# energy_meter_blk.net
KiCad netlist of a schematic drawn in Altium Designer
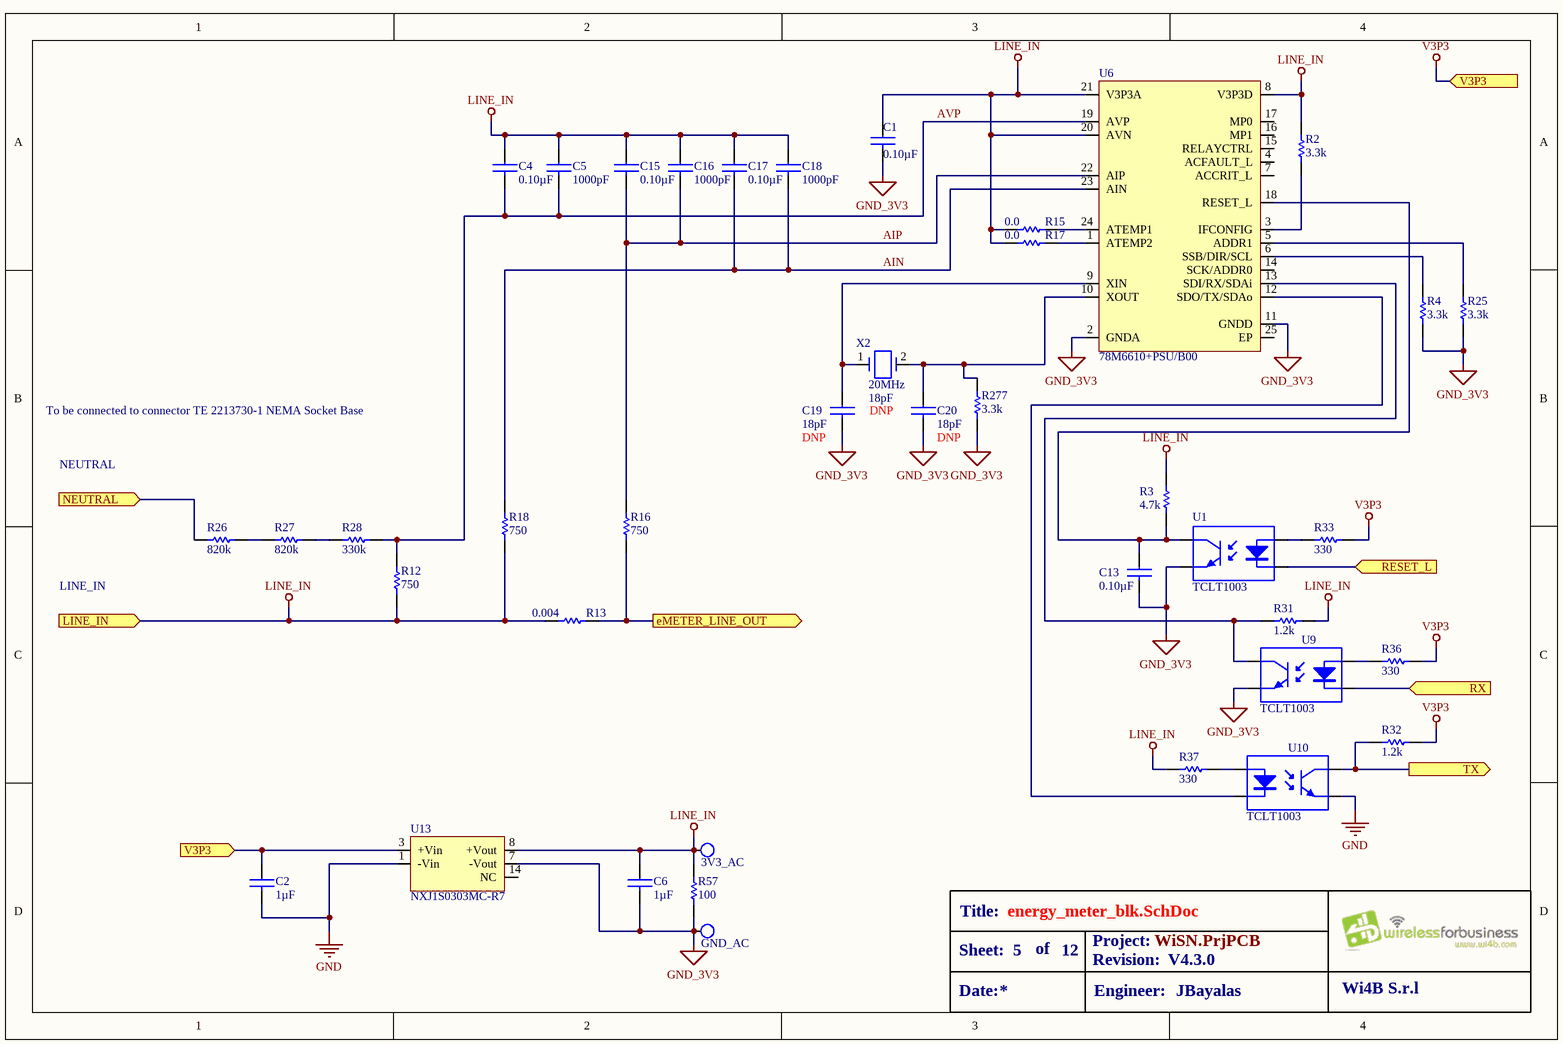
[diagram p0: energy_meter_blk.SchDoc]

(export (version "E")
  (design (tool "Eeschema 10.0.6"))
  (components
    (comp (ref "3V3_AC")
      (value "TestPad TH")
      (footprint "TestPad TH")
      (libsource (lib "Wilamp-st") (part "TestPad TH"))
    )
    (comp (ref "C1")
      (value "0.10µF")
      (footprint "C0402")
      (description "CAP CER 0.1UF 50V X7R 0402")
      (fields (field (name "MPN") "GRM155R71H104ME14D"))
      (libsource (lib "Capacitor") (part "GRM155R71H104ME14D"))
    )
    (comp (ref "C2")
      (value "1µF")
      (footprint "C0603")
      (description "CAP CER 1UF 16V X7R 0603")
      (fields (field (name "MPN") "GRM188R71C105KA12D"))
      (libsource (lib "Capacitor") (part "GRM188R71C105KA12D"))
    )
    (comp (ref "C4")
      (value "0.10µF")
      (footprint "C0402")
      (description "CAP CER 0.1UF 50V X7R 0402")
      (fields (field (name "MPN") "GRM155R71H104ME14D"))
      (libsource (lib "Capacitor") (part "GRM155R71H104ME14D"))
    )
    (comp (ref "C5")
      (value "1000pF")
      (footprint "C0402")
      (description "CAP CER 1000PF 50V NP0 0402")
      (fields (field (name "MPN") "GRM1555C1H102JA01D"))
      (libsource (lib "Capacitor") (part "GRM1555C1H102JA01D"))
    )
    (comp (ref "C6")
      (value "1µF")
      (footprint "C0603")
      (description "CAP CER 1UF 16V X7R 0603")
      (fields (field (name "MPN") "GRM188R71C105KA12D"))
      (libsource (lib "Capacitor") (part "GRM188R71C105KA12D"))
    )
    (comp (ref "C13")
      (value "0.10µF")
      (footprint "C0402")
      (description "CAP CER 0.1UF 50V X7R 0402")
      (fields (field (name "MPN") "GRM155R71H104ME14D"))
      (libsource (lib "Capacitor") (part "GRM155R71H104ME14D"))
    )
    (comp (ref "C15")
      (value "0.10µF")
      (footprint "C0402")
      (description "CAP CER 0.1UF 50V X7R 0402")
      (fields (field (name "MPN") "GRM155R71H104ME14D"))
      (libsource (lib "Capacitor") (part "GRM155R71H104ME14D"))
    )
    (comp (ref "C16")
      (value "1000pF")
      (footprint "C0402")
      (description "CAP CER 1000PF 50V NP0 0402")
      (fields (field (name "MPN") "GRM1555C1H102JA01D"))
      (libsource (lib "Capacitor") (part "GRM1555C1H102JA01D"))
    )
    (comp (ref "C17")
      (value "0.10µF")
      (footprint "C0402")
      (description "CAP CER 0.1UF 50V X7R 0402")
      (fields (field (name "MPN") "GRM155R71H104ME14D"))
      (libsource (lib "Capacitor") (part "GRM155R71H104ME14D"))
    )
    (comp (ref "C18")
      (value "1000pF")
      (footprint "C0402")
      (description "CAP CER 1000PF 50V NP0 0402")
      (fields (field (name "MPN") "GRM1555C1H102JA01D"))
      (libsource (lib "Capacitor") (part "GRM1555C1H102JA01D"))
    )
    (comp (ref "C19")
      (value "18pF")
      (footprint "C0402")
      (description "CAP CER 18PF 50V NP0 0402")
      (fields (field (name "MPN") "GRM1555C1H180FA01D") (field (name "DNP") "DNP"))
      (libsource (lib "Capacitor") (part "GRM1555C1H180FA01D"))
    )
    (comp (ref "C20")
      (value "18pF")
      (footprint "C0402")
      (description "CAP CER 18PF 50V NP0 0402")
      (fields (field (name "MPN") "GRM1555C1H180FA01D") (field (name "DNP") "DNP"))
      (libsource (lib "Capacitor") (part "GRM1555C1H180FA01D"))
    )
    (comp (ref "GND_AC")
      (value "TestPad TH")
      (footprint "TestPad TH")
      (libsource (lib "Wilamp-st") (part "TestPad TH"))
    )
    (comp (ref "R2")
      (value "3.3k")
      (footprint "R0402")
      (description "RES SMD 3.3K OHM 1% 1/16W 0402")
      (fields (field (name "MPN") "CRCW04023K30FKED"))
      (libsource (lib "Res") (part "CRCW04023K30FKED"))
    )
    (comp (ref "R3")
      (value "4.7k")
      (footprint "R0402")
      (description "RES SMD 4.7K OHM 1% 1/10W 0402")
      (fields (field (name "MPN") "ERJ-2RKF4701X"))
      (libsource (lib "Res") (part "ERJ-2RKF4701X"))
    )
    (comp (ref "R4")
      (value "3.3k")
      (footprint "R0402")
      (description "RES SMD 3.3K OHM 1% 1/16W 0402")
      (fields (field (name "MPN") "CRCW04023K30FKED"))
      (libsource (lib "Res") (part "CRCW04023K30FKED"))
    )
    (comp (ref "R12")
      (value "750")
      (footprint "R0603")
      (description "RES SMD 750 OHM 1% 1/10W 0603")
      (fields (field (name "MPN") "CRCW0603750RFKEA"))
      (libsource (lib "Res") (part "CRCW0603750RFKEA"))
    )
    (comp (ref "R13")
      (value "CRE2512-FZ-R004E-3")
      (footprint "R2512")
      (description "RES SMD 0.004 OHM 1% 3W 2512")
      (fields
        (field (name "MANUFACTURER") "Bourns Inc.")
        (field (name "TOLERANCE") "±1%")
        (field (name "RESISTANCE (OHMS)") "0.004")
      )
      (libsource (lib "Wilamp") (part "CRE2512-FZ-R004E-3"))
    )
    (comp (ref "R15")
      (value "0.0")
      (footprint "R0603")
      (description "RES SMD 0.0OHM JUMPER 1/10W 0603")
      (fields (field (name "MPN") "CRCW06030000Z0EA"))
      (libsource (lib "Res") (part "CRCW06030000Z0EA"))
    )
    (comp (ref "R16")
      (value "750")
      (footprint "R0603")
      (description "RES SMD 750 OHM 1% 1/10W 0603")
      (fields (field (name "MPN") "CRCW0603750RFKEA"))
      (libsource (lib "Res") (part "CRCW0603750RFKEA"))
    )
    (comp (ref "R17")
      (value "0.0")
      (footprint "R0603")
      (description "RES SMD 0.0OHM JUMPER 1/10W 0603")
      (fields (field (name "MPN") "CRCW06030000Z0EA"))
      (libsource (lib "Res") (part "CRCW06030000Z0EA"))
    )
    (comp (ref "R18")
      (value "750")
      (footprint "R0603")
      (description "RES SMD 750 OHM 1% 1/10W 0603")
      (fields (field (name "MPN") "CRCW0603750RFKEA"))
      (libsource (lib "Res") (part "CRCW0603750RFKEA"))
    )
    (comp (ref "R25")
      (value "3.3k")
      (footprint "R0402")
      (description "RES SMD 3.3K OHM 1% 1/16W 0402")
      (fields (field (name "MPN") "CRCW04023K30FKED"))
      (libsource (lib "Res") (part "CRCW04023K30FKED"))
    )
    (comp (ref "R26")
      (value "820k")
      (footprint "R1206")
      (description "RES SMD 820K OHM 1% 1/4W 1206")
      (fields (field (name "MPN") "CRCW1206820KFKEA"))
      (libsource (lib "Res") (part "CRCW1206820KFKEA"))
    )
    (comp (ref "R27")
      (value "820k")
      (footprint "R1206")
      (description "RES SMD 820K OHM 1% 1/4W 1206")
      (fields (field (name "MPN") "CRCW1206820KFKEA"))
      (libsource (lib "Res") (part "CRCW1206820KFKEA"))
    )
    (comp (ref "R28")
      (value "330k")
      (footprint "R1206")
      (description "RES SMD 330K OHM 1% 1/4W 1206")
      (fields (field (name "MPN") "CRCW1206330KFKEA"))
      (libsource (lib "Res") (part "CRCW1206330KFKEA"))
    )
    (comp (ref "R31")
      (value "1.2k")
      (footprint "RESC1005X40N")
      (description "RES SMD 1.2K OHM 1% 1/16W 0402")
      (fields (field (name "MPN") "RC0402FR-071K2L"))
      (libsource (lib "Res") (part "RC0402FR-071K2L"))
    )
    (comp (ref "R32")
      (value "1.2k")
      (footprint "RESC1005X40N")
      (description "RES SMD 1.2K OHM 1% 1/16W 0402")
      (fields (field (name "MPN") "RC0402FR-071K2L"))
      (libsource (lib "Res") (part "RC0402FR-071K2L"))
    )
    (comp (ref "R33")
      (value "330")
      (footprint "R0402")
      (description "RES SMD 330 OHM 1% 1/16W 0402")
      (fields (field (name "MPN") "CRCW0402330RFKED"))
      (libsource (lib "Res") (part "CRCW0402330RFKED"))
    )
    (comp (ref "R36")
      (value "330")
      (footprint "R0402")
      (description "RES SMD 330 OHM 1% 1/16W 0402")
      (fields (field (name "MPN") "CRCW0402330RFKED"))
      (libsource (lib "Res") (part "CRCW0402330RFKED"))
    )
    (comp (ref "R37")
      (value "330")
      (footprint "R0402")
      (description "RES SMD 330 OHM 1% 1/16W 0402")
      (fields (field (name "MPN") "CRCW0402330RFKED"))
      (libsource (lib "Res") (part "CRCW0402330RFKED"))
    )
    (comp (ref "R57")
      (value "100")
      (footprint "R1206")
      (description "RES 100 OHM 5% 1/4W 1206")
      (fields (field (name "MPN") "RMCF1206JT100R"))
      (libsource (lib "Res") (part "RMCF1206JT100R"))
    )
    (comp (ref "R277")
      (value "3.3k")
      (footprint "R0402")
      (description "RES SMD 3.3K OHM 1% 1/16W 0402")
      (fields (field (name "MPN") "CRCW04023K30FKED"))
      (libsource (lib "Res") (part "CRCW04023K30FKED"))
    )
    (comp (ref "U1")
      (value "TCLT1003")
      (footprint "SOP-4L")
      (description "OPTOISOLATR 5KV TRANSISTOR 4-SOP")
      (fields (field (name "MPN") "TCLT1003"))
      (libsource (lib "IC") (part "TCLT1003"))
    )
    (comp (ref "U6")
      (value "78M6610+PSU/B00")
      (footprint "QFN-24 (4X4mm)")
      (description "IC ENERGY MEASURMENT 1PH 24TQFN")
      (fields
        (field (name "MANUFACTURER") "Maxim Integrated")
        (field (name "MANUFACTURER PART NUMBER") "78M6610+PSU/B00")
      )
      (libsource (lib "Wilamp") (part "78M6610+PSU/B00"))
    )
    (comp (ref "U9")
      (value "TCLT1003")
      (footprint "SOP-4L")
      (description "OPTOISOLATR 5KV TRANSISTOR 4-SOP")
      (fields (field (name "MPN") "TCLT1003"))
      (libsource (lib "IC") (part "TCLT1003"))
    )
    (comp (ref "U10")
      (value "TCLT1003")
      (footprint "SOP-4L")
      (description "OPTOISOLATR 5KV TRANSISTOR 4-SOP")
      (fields (field (name "MPN") "TCLT1003"))
      (libsource (lib "IC") (part "TCLT1003"))
    )
    (comp (ref "U13")
      (value "NXJ1S0303MC-R7")
      (footprint "NXJ1S0303MC-R7")
      (description "Isolated DC/DC Converters 1W 3.3Vin 3.3Vout 333mA SM")
      (fields (field (name "MPN") "NXJ1S0303MC-R7"))
      (libsource (lib "IC") (part "NXJ1S0303MC-R7"))
    )
    (comp (ref "X2")
      (value "ABLS7M-20.000MHZ-B-2-T")
      (footprint "ABLS7M (crystal)")
      (description "CRYSTAL 20.000 MHZ 18PF SMT")
      (fields
        (field (name "MANUFACTURER") "Abracon LLC")
        (field (name "FREQUENCY") "20MHz")
        (field (name "LOAD CAPACITANCE") "18pF")
        (field (name "DNP") "DNP")
      )
      (libsource (lib "Wilamp") (part "ABLS7M-20.000MHZ-B-2-T"))
    )
  )
  (nets
    (net (code "1") (name "/AIN") (class "Default")
      (node (ref "C17") (pin "2") (pinfunction "2_2") (pintype "passive"))
      (node (ref "C18") (pin "2") (pinfunction "2_2") (pintype "passive"))
      (node (ref "R18") (pin "2") (pinfunction "2_2") (pintype "passive"))
      (node (ref "U6") (pin "23") (pinfunction "AIN_23") (pintype "passive"))
    )
    (net (code "2") (name "/AIP") (class "Default")
      (node (ref "C15") (pin "2") (pinfunction "2_2") (pintype "passive"))
      (node (ref "C16") (pin "2") (pinfunction "2_2") (pintype "passive"))
      (node (ref "R16") (pin "2") (pinfunction "2_2") (pintype "passive"))
      (node (ref "U6") (pin "22") (pinfunction "AIP_22") (pintype "passive"))
    )
    (net (code "3") (name "/AVP") (class "Default")
      (node (ref "C4") (pin "2") (pinfunction "2_2") (pintype "passive"))
      (node (ref "C5") (pin "2") (pinfunction "2_2") (pintype "passive"))
      (node (ref "R12") (pin "2") (pinfunction "2_2") (pintype "passive"))
      (node (ref "R28") (pin "2") (pinfunction "2_2") (pintype "passive"))
      (node (ref "U6") (pin "19") (pinfunction "AVP_19") (pintype "passive"))
    )
    (net (code "4") (name "/NEUTRAL") (class "Default")
      (node (ref "R26") (pin "1") (pinfunction "1_1") (pintype "passive"))
    )
    (net (code "5") (name "/RESET_L") (class "Default")
      (node (ref "U1") (pin "2") (pinfunction "K_2") (pintype "passive"))
    )
    (net (code "6") (name "/RX") (class "Default")
      (node (ref "U9") (pin "2") (pinfunction "K_2") (pintype "passive"))
    )
    (net (code "7") (name "/TX") (class "Default")
      (node (ref "R32") (pin "1") (pinfunction "1_1") (pintype "passive"))
      (node (ref "U10") (pin "4") (pinfunction "A/K_4") (pintype "passive"))
    )
    (net (code "8") (name "/eMETER_LINE_OUT") (class "Default")
      (node (ref "R13") (pin "2") (pinfunction "2_2") (pintype "passive"))
      (node (ref "R16") (pin "1") (pinfunction "1_1") (pintype "passive"))
    )
    (net (code "9") (name "GND") (class "Default")
      (node (ref "C2") (pin "2") (pinfunction "2_2") (pintype "passive"))
      (node (ref "U10") (pin "3") (pinfunction "A/K_3") (pintype "passive"))
      (node (ref "U13") (pin "1") (pinfunction "-Vin_1") (pintype "passive"))
    )
    (net (code "10") (name "GND_3V3") (class "Default")
      (node (ref "C1") (pin "2") (pinfunction "2_2") (pintype "passive"))
      (node (ref "C13") (pin "2") (pinfunction "2_2") (pintype "passive"))
      (node (ref "C19") (pin "2") (pinfunction "2_2") (pintype "passive"))
      (node (ref "C20") (pin "2") (pinfunction "2_2") (pintype "passive"))
      (node (ref "C6") (pin "2") (pinfunction "2_2") (pintype "passive"))
      (node (ref "GND_AC") (pin "1") (pinfunction "1_1") (pintype "passive"))
      (node (ref "R25") (pin "1") (pinfunction "1_1") (pintype "passive"))
      (node (ref "R277") (pin "1") (pinfunction "1_1") (pintype "passive"))
      (node (ref "R4") (pin "1") (pinfunction "1_1") (pintype "passive"))
      (node (ref "R57") (pin "2") (pinfunction "2_2") (pintype "passive"))
      (node (ref "U1") (pin "3") (pinfunction "A/K_3") (pintype "passive"))
      (node (ref "U13") (pin "7") (pinfunction "-Vout_7") (pintype "passive"))
      (node (ref "U6") (pin "11") (pinfunction "GNDD_11") (pintype "passive"))
      (node (ref "U6") (pin "2") (pinfunction "GNDA_2") (pintype "passive"))
      (node (ref "U9") (pin "3") (pinfunction "A/K_3") (pintype "passive"))
    )
    (net (code "11") (name "LINE_IN") (class "Default")
      (node (ref "3V3_AC") (pin "1") (pinfunction "1_1") (pintype "passive"))
      (node (ref "C1") (pin "1") (pinfunction "1_1") (pintype "passive"))
      (node (ref "C15") (pin "1") (pinfunction "1_1") (pintype "passive"))
      (node (ref "C16") (pin "1") (pinfunction "1_1") (pintype "passive"))
      (node (ref "C17") (pin "1") (pinfunction "1_1") (pintype "passive"))
      (node (ref "C18") (pin "1") (pinfunction "1_1") (pintype "passive"))
      (node (ref "C4") (pin "1") (pinfunction "1_1") (pintype "passive"))
      (node (ref "C5") (pin "1") (pinfunction "1_1") (pintype "passive"))
      (node (ref "C6") (pin "1") (pinfunction "1_1") (pintype "passive"))
      (node (ref "R12") (pin "1") (pinfunction "1_1") (pintype "passive"))
      (node (ref "R13") (pin "1") (pinfunction "1_1") (pintype "passive"))
      (node (ref "R15") (pin "1") (pinfunction "1_1") (pintype "passive"))
      (node (ref "R17") (pin "1") (pinfunction "1_1") (pintype "passive"))
      (node (ref "R18") (pin "1") (pinfunction "1_1") (pintype "passive"))
      (node (ref "R2") (pin "2") (pinfunction "2_2") (pintype "passive"))
      (node (ref "R3") (pin "2") (pinfunction "2_2") (pintype "passive"))
      (node (ref "R31") (pin "2") (pinfunction "2_2") (pintype "passive"))
      (node (ref "R37") (pin "1") (pinfunction "1_1") (pintype "passive"))
      (node (ref "R57") (pin "1") (pinfunction "1_1") (pintype "passive"))
      (node (ref "U13") (pin "8") (pinfunction "+Vout_8") (pintype "passive"))
      (node (ref "U6") (pin "20") (pinfunction "AVN_20") (pintype "passive"))
      (node (ref "U6") (pin "21") (pinfunction "V3P3A_21") (pintype "passive"))
      (node (ref "U6") (pin "8") (pinfunction "V3P3D_8") (pintype "passive"))
    )
    (net (code "12") (name "Net-(R26-Pad2)") (class "Default")
      (node (ref "R26") (pin "2") (pinfunction "2_2") (pintype "passive"))
      (node (ref "R27") (pin "1") (pinfunction "1_1") (pintype "passive"))
    )
    (net (code "13") (name "Net-(R27-Pad2)") (class "Default")
      (node (ref "R27") (pin "2") (pinfunction "2_2") (pintype "passive"))
      (node (ref "R28") (pin "1") (pinfunction "1_1") (pintype "passive"))
    )
    (net (code "14") (name "Net-(U1-A)") (class "Default")
      (node (ref "R33") (pin "1") (pinfunction "1_1") (pintype "passive"))
      (node (ref "U1") (pin "1") (pinfunction "A_1") (pintype "passive"))
    )
    (net (code "15") (name "Net-(U6-ADDR1)") (class "Default")
      (node (ref "R25") (pin "2") (pinfunction "2_2") (pintype "passive"))
      (node (ref "U6") (pin "5") (pinfunction "ADDR1_5") (pintype "passive"))
    )
    (net (code "16") (name "Net-(U6-ATEMP1)") (class "Default")
      (node (ref "R15") (pin "2") (pinfunction "2_2") (pintype "passive"))
      (node (ref "U6") (pin "24") (pinfunction "ATEMP1_24") (pintype "passive"))
    )
    (net (code "17") (name "Net-(U6-ATEMP2)") (class "Default")
      (node (ref "R17") (pin "2") (pinfunction "2_2") (pintype "passive"))
      (node (ref "U6") (pin "1") (pinfunction "ATEMP2_1") (pintype "passive"))
    )
    (net (code "18") (name "Net-(U6-IFCONFIG)") (class "Default")
      (node (ref "R2") (pin "1") (pinfunction "1_1") (pintype "passive"))
      (node (ref "U6") (pin "3") (pinfunction "IFCONFIG_3") (pintype "passive"))
    )
    (net (code "19") (name "Net-(U6-RESET_L)") (class "Default")
      (node (ref "C13") (pin "1") (pinfunction "1_1") (pintype "passive"))
      (node (ref "R3") (pin "1") (pinfunction "1_1") (pintype "passive"))
      (node (ref "U1") (pin "4") (pinfunction "A/K_4") (pintype "passive"))
      (node (ref "U6") (pin "18") (pinfunction "RESET_L_18") (pintype "passive"))
    )
    (net (code "20") (name "Net-(U6-SDI{slash}RX{slash}SDAi)") (class "Default")
      (node (ref "R31") (pin "1") (pinfunction "1_1") (pintype "passive"))
      (node (ref "U6") (pin "13") (pinfunction "SDI/RX/SDAi_13") (pintype "passive"))
      (node (ref "U9") (pin "4") (pinfunction "A/K_4") (pintype "passive"))
    )
    (net (code "21") (name "Net-(U6-SSB{slash}DIR{slash}SCL)") (class "Default")
      (node (ref "R4") (pin "2") (pinfunction "2_2") (pintype "passive"))
      (node (ref "U6") (pin "6") (pinfunction "SSB/DIR/SCL_6") (pintype "passive"))
    )
    (net (code "22") (name "Net-(U6-XIN)") (class "Default")
      (node (ref "C19") (pin "1") (pinfunction "1_1") (pintype "passive"))
      (node (ref "U6") (pin "9") (pinfunction "XIN_9") (pintype "passive"))
      (node (ref "X2") (pin "1") (pinfunction "1_1") (pintype "passive"))
    )
    (net (code "23") (name "Net-(U6-XOUT)") (class "Default")
      (node (ref "C20") (pin "1") (pinfunction "1_1") (pintype "passive"))
      (node (ref "R277") (pin "2") (pinfunction "2_2") (pintype "passive"))
      (node (ref "U6") (pin "10") (pinfunction "XOUT_10") (pintype "passive"))
      (node (ref "X2") (pin "2") (pinfunction "2_2") (pintype "passive"))
    )
    (net (code "24") (name "Net-(U9-A)") (class "Default")
      (node (ref "R36") (pin "1") (pinfunction "1_1") (pintype "passive"))
      (node (ref "U9") (pin "1") (pinfunction "A_1") (pintype "passive"))
    )
    (net (code "25") (name "Net-(U10-A)") (class "Default")
      (node (ref "R37") (pin "2") (pinfunction "2_2") (pintype "passive"))
      (node (ref "U10") (pin "1") (pinfunction "A_1") (pintype "passive"))
    )
    (net (code "26") (name "Net-(U10-K)") (class "Default")
      (node (ref "U10") (pin "2") (pinfunction "K_2") (pintype "passive"))
      (node (ref "U6") (pin "12") (pinfunction "SDO/TX/SDAo_12") (pintype "passive"))
    )
    (net (code "27") (name "V3P3") (class "Default")
      (node (ref "C2") (pin "1") (pinfunction "1_1") (pintype "passive"))
      (node (ref "R32") (pin "2") (pinfunction "2_2") (pintype "passive"))
      (node (ref "R33") (pin "2") (pinfunction "2_2") (pintype "passive"))
      (node (ref "R36") (pin "2") (pinfunction "2_2") (pintype "passive"))
      (node (ref "U13") (pin "3") (pinfunction "+Vin_3") (pintype "passive"))
    )
    (net (code "28") (name "unconnected-(U6-ACCRIT_L-Pad7)") (class "Default")
      (node (ref "U6") (pin "7") (pinfunction "ACCRIT_L_7") (pintype "passive"))
    )
    (net (code "29") (name "unconnected-(U6-ACFAULT_L-Pad4)") (class "Default")
      (node (ref "U6") (pin "4") (pinfunction "ACFAULT_L_4") (pintype "passive"))
    )
    (net (code "30") (name "unconnected-(U6-EP-Pad25)") (class "Default")
      (node (ref "U6") (pin "25") (pinfunction "EP_25") (pintype "passive"))
    )
    (net (code "31") (name "unconnected-(U6-MP0-Pad17)") (class "Default")
      (node (ref "U6") (pin "17") (pinfunction "MP0_17") (pintype "passive"))
    )
    (net (code "32") (name "unconnected-(U6-MP1-Pad16)") (class "Default")
      (node (ref "U6") (pin "16") (pinfunction "MP1_16") (pintype "passive"))
    )
    (net (code "33") (name "unconnected-(U6-RELAYCTRL-Pad15)") (class "Default")
      (node (ref "U6") (pin "15") (pinfunction "RELAYCTRL_15") (pintype "passive"))
    )
    (net (code "34") (name "unconnected-(U6-SCK{slash}ADDR0-Pad14)") (class "Default")
      (node (ref "U6") (pin "14") (pinfunction "SCK/ADDR0_14") (pintype "passive"))
    )
    (net (code "35") (name "unconnected-(U13-NC-Pad14)") (class "Default")
      (node (ref "U13") (pin "14") (pinfunction "NC_14") (pintype "passive"))
    )
  )
)
